# AirScout_SchematicsV0_Spannungsversorgun.net
KiCad netlist of a schematic drawn in Altium Designer
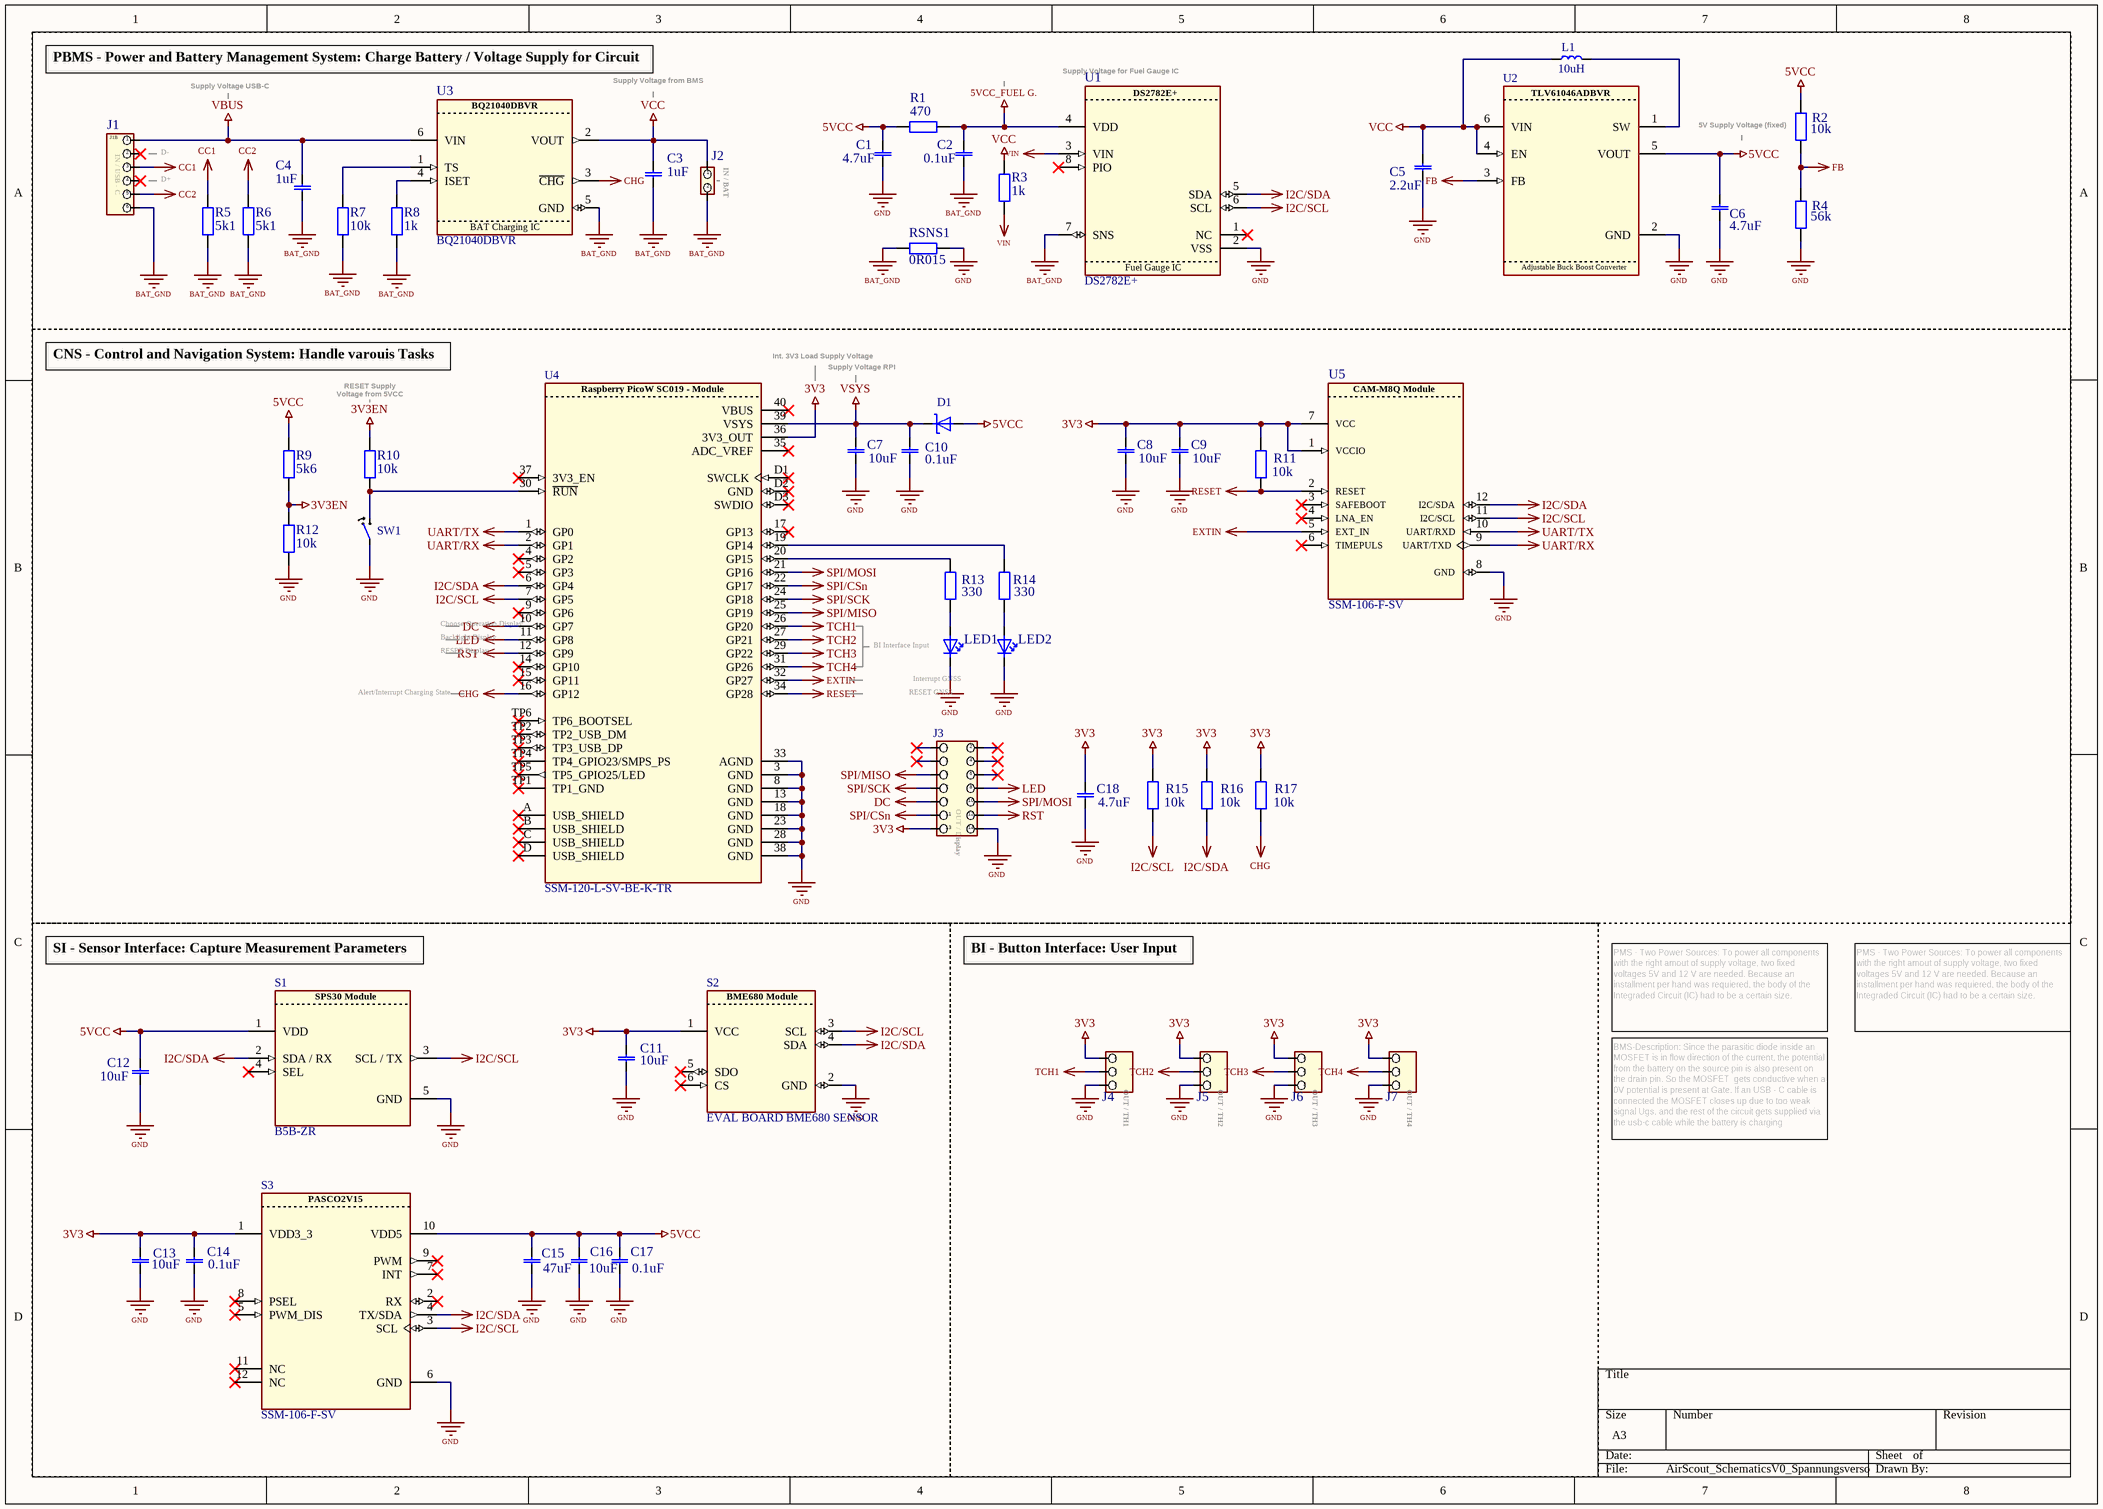
[diagram p0: AirScout_SchematicsV0_Spannungsversorgung.SchDoc]

(export (version "E")
  (design (tool "Eeschema 10.0.6"))
  (components
    (comp (ref "C1")
      (value "4.7uF")
      (footprint "CAPC340180_140N_KEM")
      (description "CAP CER 4.7UF 50V X7R 1206")
      (fields (field (name "Comment") "CL31B475KBHNFNE"))
      (libsource (lib "AirScoutSchLib") (part "CAP"))
    )
    (comp (ref "C2")
      (value "0.1uF")
      (footprint "CAPC340180_140N_KEM")
      (description "CAP CER 0.1UF 50V X7R 1206")
      (fields (field (name "Comment") "C1206C104K5RACTU"))
      (libsource (lib "AirScoutSchLib") (part "CAP"))
    )
    (comp (ref "C3")
      (value "1uF")
      (footprint "CAPC340180_140N_KEM")
      (description "CAP CER 1UF 25V X7R 1206")
      (fields (field (name "Comment") "C1206C105K3RACTU"))
      (libsource (lib "AirScoutSchLib") (part "CAP"))
    )
    (comp (ref "C4")
      (value "1uF")
      (footprint "CAPC340180_140N_KEM")
      (description "CAP CER 1UF 25V X7R 1206")
      (fields (field (name "Comment") "C1206C105K3RACTU"))
      (libsource (lib "AirScoutSchLib") (part "CAP"))
    )
    (comp (ref "C5")
      (value "2.2uF")
      (footprint "CAPC340180_140N_KEM")
      (description "CAP CER 2.2UF 50V X7R 1206")
      (fields (field (name "Comment") "CL31B225KBHNNNE"))
      (libsource (lib "AirScoutSchLib") (part "CAP"))
    )
    (comp (ref "C6")
      (value "4.7uF")
      (footprint "CAPC340180_140N_KEM")
      (description "CAP CER 4.7UF 50V X7R 1206")
      (fields (field (name "Comment") "CL31B475KBHNFNE"))
      (libsource (lib "AirScoutSchLib") (part "CAP"))
    )
    (comp (ref "C7")
      (value "10uF")
      (footprint "CAPC340180_140N_KEM")
      (description "CAP CER 10UF 25V X7R 1206")
      (fields (field (name "Comment") "CL31B106KAHNNNE"))
      (libsource (lib "AirScoutSchLib") (part "CAP"))
    )
    (comp (ref "C8")
      (value "10uF")
      (footprint "CAPC340180_140N_KEM")
      (description "CAP CER 10UF 25V X7R 1206")
      (fields (field (name "Comment") "CL31B106KAHNNNE"))
      (libsource (lib "AirScoutSchLib") (part "CAP"))
    )
    (comp (ref "C9")
      (value "10uF")
      (footprint "CAPC340180_140N_KEM")
      (description "CAP CER 10UF 25V X7R 1206")
      (fields (field (name "Comment") "CL31B106KAHNNNE"))
      (libsource (lib "AirScoutSchLib") (part "CAP"))
    )
    (comp (ref "C10")
      (value "0.1uF")
      (footprint "CAPC340180_140N_KEM")
      (description "CAP CER 0.1UF 50V X7R 1206")
      (fields (field (name "Comment") "C1206C104K5RACTU"))
      (libsource (lib "AirScoutSchLib") (part "CAP"))
    )
    (comp (ref "C11")
      (value "10uF")
      (footprint "CAPC340180_140N_KEM")
      (description "CAP CER 10UF 25V X7R 1206")
      (fields (field (name "Comment") "CL31B106KAHNNNE"))
      (libsource (lib "AirScoutSchLib") (part "CAP"))
    )
    (comp (ref "C12")
      (value "10uF")
      (footprint "CAPC340180_140N_KEM")
      (description "CAP CER 10UF 25V X7R 1206")
      (fields (field (name "Comment") "CL31B106KAHNNNE"))
      (libsource (lib "AirScoutSchLib") (part "CAP"))
    )
    (comp (ref "C13")
      (value "10uF")
      (footprint "CAPC340180_140N_KEM")
      (description "CAP CER 10UF 25V X7R 1206")
      (fields (field (name "Comment") "CL31B106KAHNNNE"))
      (libsource (lib "AirScoutSchLib") (part "CAP"))
    )
    (comp (ref "C14")
      (value "0.1uF")
      (footprint "CAPC340180_140N_KEM")
      (description "CAP CER 0.1UF 50V X7R 1206")
      (fields (field (name "Comment") "C1206C104K5RACTU"))
      (libsource (lib "AirScoutSchLib") (part "CAP"))
    )
    (comp (ref "C15")
      (value "47uF")
      (footprint "CAPC340180_140N_KEM")
      (description "CAP CER 10UF 25V X7R 1206")
      (fields (field (name "Comment") "CL31B106KAHNNNE"))
      (libsource (lib "AirScoutSchLib") (part "CAP"))
    )
    (comp (ref "C16")
      (value "10uF")
      (footprint "CAPC340180_140N_KEM")
      (description "CAP CER 10UF 25V X7R 1206")
      (fields (field (name "Comment") "CL31B106KAHNNNE"))
      (libsource (lib "AirScoutSchLib") (part "CAP"))
    )
    (comp (ref "C17")
      (value "0.1uF")
      (footprint "CAPC340180_140N_KEM")
      (description "CAP CER 0.1UF 50V X7R 1206")
      (fields (field (name "Comment") "C1206C104K5RACTU"))
      (libsource (lib "AirScoutSchLib") (part "CAP"))
    )
    (comp (ref "C18")
      (value "4.7uF")
      (footprint "CAPC340180_140N_KEM")
      (description "CAP CER 4.7UF 50V X7R 1206")
      (fields (field (name "Comment") "CL31B475KBHNFNE"))
      (libsource (lib "AirScoutSchLib") (part "CAP"))
    )
    (comp (ref "D1")
      (value "B240A-13-F")
      (footprint "DIOM5226X230N")
      (description "DIODE SCHOTTKY 40V 2A SMA")
      (libsource (lib "AirScoutSchLib") (part "Diode-Schottky"))
    )
    (comp (ref "J1")
      (value "B6B-PH-K-S")
      (footprint "JST_B6B-PH-K-S")
      (description "CONN HEADER VERT 6POS 2MM")
      (libsource (lib "AirScoutSchLib") (part "CON6x1"))
    )
    (comp (ref "J2")
      (value "B02B-PASK-1")
      (footprint "JST_B2B-PH-K-S")
      (description "CONN HEADER VERT 2POS 2MM")
      (libsource (lib "AirScoutSchLib") (part "CON2x1_vertical"))
    )
    (comp (ref "J3")
      (value "0705430013")
      (footprint "CONN_SDA-70543-XXXX_14_MOL")
      (description "CONN HEADER VERT 14POS 2.54MM")
      (libsource (lib "AirScoutSchLib") (part "CON7x2"))
    )
    (comp (ref "J4")
      (value "0705430002")
      (footprint "MOLEX_70543-0037")
      (description "CONN HEADER VERT 3POS 2.54MM")
      (libsource (lib "AirScoutSchLib") (part "CON 3x1"))
    )
    (comp (ref "J5")
      (value "0705430002")
      (footprint "MOLEX_70543-0037")
      (description "CONN HEADER VERT 3POS 2.54MM")
      (libsource (lib "AirScoutSchLib") (part "CON 3x1"))
    )
    (comp (ref "J6")
      (value "0705430002")
      (footprint "MOLEX_70543-0037")
      (description "CONN HEADER VERT 3POS 2.54MM")
      (libsource (lib "AirScoutSchLib") (part "CON 3x1"))
    )
    (comp (ref "J7")
      (value "0705430002")
      (footprint "MOLEX_70543-0037")
      (description "CONN HEADER VERT 3POS 2.54MM")
      (libsource (lib "AirScoutSchLib") (part "CON 3x1"))
    )
    (comp (ref "L1")
      (value "10uH")
      (footprint "IND_FDSD0420-H-100M=P3")
      (description "FIXED IND 10UH 1.7A 200 MOHM SMD")
      (fields (field (name "Comment") "FDSD0420-H-100M=P3"))
      (libsource (lib "AirScoutSchLib") (part "Inductor"))
    )
    (comp (ref "LED1")
      (value "LTST-C150GKT")
      (footprint "LED_LTST-C150GKT_LTO")
      (description "LED GREEN CLEAR 1206 SMD")
      (libsource (lib "AirScoutSchLib") (part "LED"))
    )
    (comp (ref "LED2")
      (value "LTST-C150KRKT")
      (footprint "LED_LTST-C150GKT_LTO")
      (description "LED RED CLEAR 1206 SMD")
      (libsource (lib "AirScoutSchLib") (part "LED"))
    )
    (comp (ref "R1")
      (value "470")
      (footprint "RESC3116X65N")
      (description "RES 470 OHM 1% 1/4W 1206")
      (fields (field (name "Comment") "CRGCQ1206F470R"))
      (libsource (lib "AirScoutSchLib") (part "RES"))
    )
    (comp (ref "R2")
      (value "10k")
      (footprint "RESC3116X65N")
      (description "RES 10K OHM 1% 1/4W 1206")
      (fields (field (name "Comment") "RC1206FR-0710KL"))
      (libsource (lib "AirScoutSchLib") (part "RES"))
    )
    (comp (ref "R3")
      (value "1k")
      (footprint "RESC3116X65N")
      (description "RES 1K OHM 1% 1/2W 1206")
      (fields (field (name "Comment") "RNCP1206FTD1K00"))
      (libsource (lib "AirScoutSchLib") (part "RES"))
    )
    (comp (ref "R4")
      (value "56k")
      (footprint "RESC3116X65N")
      (description "RES 56K OHM 5% 1/4W 1206")
      (fields (field (name "Comment") "RMCF1206JT56K0"))
      (libsource (lib "AirScoutSchLib") (part "RES"))
    )
    (comp (ref "R5")
      (value "5k1")
      (footprint "RESC3116X65N")
      (description "RES 5.1K OHM 5% 1/4W 1206")
      (fields (field (name "Comment") "RMCF1206JT5K10"))
      (libsource (lib "AirScoutSchLib") (part "RES"))
    )
    (comp (ref "R6")
      (value "5k1")
      (footprint "RESC3116X65N")
      (description "RES 5.1K OHM 5% 1/4W 1206")
      (fields (field (name "Comment") "RMCF1206JT5K10"))
      (libsource (lib "AirScoutSchLib") (part "RES"))
    )
    (comp (ref "R7")
      (value "10k")
      (footprint "RESC3116X65N")
      (description "RES 10K OHM 1% 1/4W 1206")
      (fields (field (name "Comment") "RC1206FR-0710KL"))
      (libsource (lib "AirScoutSchLib") (part "RES"))
    )
    (comp (ref "R8")
      (value "1k")
      (footprint "RESC3116X65N")
      (description "RES 10K OHM 1% 1/4W 1206")
      (fields (field (name "Comment") "RC1206FR-0710KL"))
      (libsource (lib "AirScoutSchLib") (part "RES"))
    )
    (comp (ref "R9")
      (value "5k6")
      (footprint "RESC3116X65N")
      (description "RES 5.6K OHM 5% 1/4W 1206")
      (fields (field (name "Comment") "RC1206JR-075K6L"))
      (libsource (lib "AirScoutSchLib") (part "RES"))
    )
    (comp (ref "R10")
      (value "10k")
      (footprint "RESC3116X65N")
      (description "RES 10K OHM 1% 1/4W 1206")
      (fields (field (name "Comment") "RC1206FR-0710KL"))
      (libsource (lib "AirScoutSchLib") (part "RES"))
    )
    (comp (ref "R11")
      (value "10k")
      (footprint "RESC3116X65N")
      (description "RES 10K OHM 1% 1/4W 1206")
      (fields (field (name "Comment") "RC1206FR-0710KL"))
      (libsource (lib "AirScoutSchLib") (part "RES"))
    )
    (comp (ref "R12")
      (value "10k")
      (footprint "RESC3116X65N")
      (description "RES 10K OHM 1% 1/4W 1206")
      (fields (field (name "Comment") "RC1206FR-0710KL"))
      (libsource (lib "AirScoutSchLib") (part "RES"))
    )
    (comp (ref "R13")
      (value "330")
      (footprint "RESC3116X65N")
      (description "RES 330 OHM 5% 1/4W 1206")
      (fields (field (name "Comment") "RMCF1206JT330R"))
      (libsource (lib "AirScoutSchLib") (part "RES"))
    )
    (comp (ref "R14")
      (value "330")
      (footprint "RESC3116X65N")
      (description "RES 330 OHM 5% 1/4W 1206")
      (fields (field (name "Comment") "RMCF1206JT330R"))
      (libsource (lib "AirScoutSchLib") (part "RES"))
    )
    (comp (ref "R15")
      (value "10k")
      (footprint "RESC3116X65N")
      (description "RES 10K OHM 1% 1/4W 1206")
      (fields (field (name "Comment") "RC1206FR-0710KL"))
      (libsource (lib "AirScoutSchLib") (part "RES"))
    )
    (comp (ref "R16")
      (value "10k")
      (footprint "RESC3116X65N")
      (description "RES 10K OHM 1% 1/4W 1206")
      (fields (field (name "Comment") "RC1206FR-0710KL"))
      (libsource (lib "AirScoutSchLib") (part "RES"))
    )
    (comp (ref "R17")
      (value "10k")
      (footprint "RESC3116X65N")
      (description "RES 10K OHM 1% 1/4W 1206")
      (fields (field (name "Comment") "RC1206FR-0710KL"))
      (libsource (lib "AirScoutSchLib") (part "RES"))
    )
    (comp (ref "RSNS1")
      (value "0R015")
      (footprint "RESC3116X65N")
      (description "RES 0.015 OHM 1% 1/4W 1206")
      (fields (field (name "Comment") "WSL1206R0150FEA"))
      (libsource (lib "AirScoutSchLib") (part "RES"))
    )
    (comp (ref "S1")
      (value "B5B-ZR")
      (footprint "CONN5_B5B-ZR_JST")
      (description "Plug: CONN HEADER VERT 5POS 1.5MM; Air Sensor Dust Sensor Box SPS30 Module: 1649-1106-ND")
      (libsource (lib "AirScoutSchLib") (part "SPS30 Module"))
    )
    (comp (ref "S2")
      (value "EVAL BOARD BME680 SENSOR")
      (footprint "PIM357")
      (description "BME680 - Gas, Feuchtigkeit, Druck, Temperatur Evaluierungsboards - Sensoren")
      (libsource (lib "AirScoutSchLib") (part "BME680 Module"))
    )
    (comp (ref "S3")
      (value "SSM-106-F-SV")
      (footprint "IFX-SMD-LG-MLGA-14-1-V_MODUL")
      (description "(2x) CONN RCPT 6POS 0.1 GOLD SMD; Sensor: EVALCO25VMINIBOARDTOBO1; EVAL BOARD")
      (libsource (lib "AirScoutSchLib") (part "PASCO2V15 Module"))
    )
    (comp (ref "SW1")
      (value "Y97KT23B2NAFP")
      (footprint "SW_PTS647SM38SMTR2LFS_CNK")
      (description "SWITCH TACTILE SPST-NO 0.05A 12V")
      (libsource (lib "AirScoutSchLib") (part "Switch"))
    )
    (comp (ref "U1")
      (value "DS2782E+")
      (footprint "SOP65P640X110-8N")
      (description "UVP (Undervoltageprotection), Battery Battery Monitor IC Lithium Ion/Polymer 8-TSSOP")
      (libsource (lib "AirScoutSchLib") (part "DS2782E+"))
    )
    (comp (ref "U2")
      (value "TLV61046ADBVR")
      (footprint "DBV0006A_M")
      (description "28-V Output Voltage Boost Converter with Power Diode and Isolation Switch 6-SOT-23 -40 to 125")
      (fields (field (name "COPYRIGHT") "Copyright (C) 2025 Ultra Librarian. All rights reserved."))
      (libsource (lib "AirScoutSchLib") (part "TLV61046ADBVR"))
    )
    (comp (ref "U3")
      (value "BQ21040DBVR")
      (footprint "SOT95P280X145-6N")
      (fields (field (name "MF") "Texas Instruments"))
      (libsource (lib "AirScoutSchLib") (part "BQ21040DBVR"))
    )
    (comp (ref "U4")
      (value "SSM-120-L-SV-BE-K-TR")
      (footprint "PicoW SC019")
      (description "(2x) CONN RCPT 20POS 0.1 GOLD SMD; PicoW: SC0918; RASPBERRY PI PICO W RP2040")
      (libsource (lib "AirScoutSchLib") (part "Raspberry PicoW SC019 Module"))
    )
    (comp (ref "U5")
      (value "SSM-106-F-SV")
      (footprint "CAM8MQ-Mod")
      (description "(2x) CONN RCPT 6POS 0.1 GOLD SMD; GPS - Module:  201880; CAM-M8Q-BREAKOUT MULTI GNSS MODU")
      (libsource (lib "AirScoutSchLib") (part "CAM-M8Q Module"))
    )
  )
  (nets
    (net (code "1") (name "3V3") (class "Default")
      (node (ref "C11") (pin "1") (pinfunction "1_1") (pintype "passive"))
      (node (ref "C13") (pin "1") (pinfunction "1_1") (pintype "passive"))
      (node (ref "C14") (pin "1") (pinfunction "1_1") (pintype "passive"))
      (node (ref "C18") (pin "1") (pinfunction "1_1") (pintype "passive"))
      (node (ref "C8") (pin "1") (pinfunction "1_1") (pintype "passive"))
      (node (ref "C9") (pin "1") (pinfunction "1_1") (pintype "passive"))
      (node (ref "J3") (pin "13") (pinfunction "13_13") (pintype "passive"))
      (node (ref "J4") (pin "1") (pinfunction "1_1") (pintype "passive"))
      (node (ref "J5") (pin "1") (pinfunction "1_1") (pintype "passive"))
      (node (ref "J6") (pin "1") (pinfunction "1_1") (pintype "passive"))
      (node (ref "J7") (pin "1") (pinfunction "1_1") (pintype "passive"))
      (node (ref "R11") (pin "2") (pinfunction "2_2") (pintype "passive"))
      (node (ref "R15") (pin "2") (pinfunction "2_2") (pintype "passive"))
      (node (ref "R16") (pin "1") (pinfunction "1_1") (pintype "passive"))
      (node (ref "R17") (pin "1") (pinfunction "1_1") (pintype "passive"))
      (node (ref "S2") (pin "1") (pinfunction "VCC_1") (pintype "power_in"))
      (node (ref "S3") (pin "1") (pinfunction "VDD3_3_1") (pintype "power_in"))
      (node (ref "U4") (pin "36") (pinfunction "3V3_OUT_36") (pintype "power_in"))
      (node (ref "U5") (pin "1") (pinfunction "VCCIO_1") (pintype "input"))
      (node (ref "U5") (pin "7") (pinfunction "VCC_7") (pintype "power_in"))
    )
    (net (code "2") (name "3V3EN") (class "Default")
      (node (ref "R10") (pin "2") (pinfunction "2_2") (pintype "passive"))
      (node (ref "R12") (pin "2") (pinfunction "2_2") (pintype "passive"))
      (node (ref "R9") (pin "1") (pinfunction "1_1") (pintype "passive"))
    )
    (net (code "3") (name "5VCC") (class "Default")
      (node (ref "C1") (pin "1") (pinfunction "1_1") (pintype "passive"))
      (node (ref "C12") (pin "1") (pinfunction "1_1") (pintype "passive"))
      (node (ref "C15") (pin "1") (pinfunction "1_1") (pintype "passive"))
      (node (ref "C16") (pin "1") (pinfunction "1_1") (pintype "passive"))
      (node (ref "C17") (pin "1") (pinfunction "1_1") (pintype "passive"))
      (node (ref "C6") (pin "2") (pinfunction "2_2") (pintype "passive"))
      (node (ref "D1") (pin "A") (pinfunction "A_A") (pintype "passive"))
      (node (ref "R1") (pin "1") (pinfunction "1_1") (pintype "passive"))
      (node (ref "R2") (pin "2") (pinfunction "2_2") (pintype "passive"))
      (node (ref "R9") (pin "2") (pinfunction "2_2") (pintype "passive"))
      (node (ref "S1") (pin "1") (pinfunction "VDD_1") (pintype "passive"))
      (node (ref "S3") (pin "10") (pinfunction "VDD5_10") (pintype "power_in"))
      (node (ref "U2") (pin "5") (pinfunction "VOUT_5") (pintype "power_in"))
    )
    (net (code "4") (name "5VCC_FUEL G.") (class "Default")
      (node (ref "C2") (pin "1") (pinfunction "1_1") (pintype "passive"))
      (node (ref "R1") (pin "2") (pinfunction "2_2") (pintype "passive"))
      (node (ref "U1") (pin "4") (pinfunction "VDD_4") (pintype "power_in"))
    )
    (net (code "5") (name "BAT_GND") (class "Default")
      (node (ref "C2") (pin "2") (pinfunction "2_2") (pintype "passive"))
      (node (ref "C3") (pin "2") (pinfunction "2_2") (pintype "passive"))
      (node (ref "C4") (pin "2") (pinfunction "2_2") (pintype "passive"))
      (node (ref "J1") (pin "6") (pinfunction "6_6") (pintype "passive"))
      (node (ref "J2") (pin "2") (pinfunction "-_2") (pintype "passive"))
      (node (ref "R5") (pin "1") (pinfunction "1_1") (pintype "passive"))
      (node (ref "R6") (pin "1") (pinfunction "1_1") (pintype "passive"))
      (node (ref "R7") (pin "1") (pinfunction "1_1") (pintype "passive"))
      (node (ref "R8") (pin "1") (pinfunction "1_1") (pintype "passive"))
      (node (ref "RSNS1") (pin "2") (pinfunction "2_2") (pintype "passive"))
      (node (ref "U1") (pin "7") (pinfunction "SNS_7") (pintype "bidirectional"))
      (node (ref "U3") (pin "5") (pinfunction "GND_5") (pintype "bidirectional"))
    )
    (net (code "6") (name "CC1") (class "Default")
      (node (ref "J1") (pin "3") (pinfunction "3_3") (pintype "passive"))
      (node (ref "R5") (pin "2") (pinfunction "2_2") (pintype "passive"))
    )
    (net (code "7") (name "CC2") (class "Default")
      (node (ref "J1") (pin "5") (pinfunction "5_5") (pintype "passive"))
      (node (ref "R6") (pin "2") (pinfunction "2_2") (pintype "passive"))
    )
    (net (code "8") (name "CHG") (class "Default")
      (node (ref "R17") (pin "2") (pinfunction "2_2") (pintype "passive"))
      (node (ref "U3") (pin "3") (pinfunction "~{CHG}_3") (pintype "output"))
      (node (ref "U4") (pin "16") (pinfunction "GP12_16") (pintype "bidirectional"))
    )
    (net (code "9") (name "DC") (class "Default")
      (node (ref "J3") (pin "9") (pinfunction "9_9") (pintype "passive"))
      (node (ref "U4") (pin "10") (pinfunction "GP7_10") (pintype "bidirectional"))
    )
    (net (code "10") (name "EXTIN") (class "Default")
      (node (ref "U4") (pin "32") (pinfunction "GP27_32") (pintype "bidirectional"))
      (node (ref "U5") (pin "5") (pinfunction "EXT_IN_5") (pintype "input"))
    )
    (net (code "11") (name "FB") (class "Default")
      (node (ref "R2") (pin "1") (pinfunction "1_1") (pintype "passive"))
      (node (ref "R4") (pin "2") (pinfunction "2_2") (pintype "passive"))
      (node (ref "U2") (pin "3") (pinfunction "FB_3") (pintype "input"))
    )
    (net (code "12") (name "GND") (class "Default")
      (node (ref "C1") (pin "2") (pinfunction "2_2") (pintype "passive"))
      (node (ref "C10") (pin "2") (pinfunction "2_2") (pintype "passive"))
      (node (ref "C11") (pin "2") (pinfunction "2_2") (pintype "passive"))
      (node (ref "C12") (pin "2") (pinfunction "2_2") (pintype "passive"))
      (node (ref "C13") (pin "2") (pinfunction "2_2") (pintype "passive"))
      (node (ref "C14") (pin "2") (pinfunction "2_2") (pintype "passive"))
      (node (ref "C15") (pin "2") (pinfunction "2_2") (pintype "passive"))
      (node (ref "C16") (pin "2") (pinfunction "2_2") (pintype "passive"))
      (node (ref "C17") (pin "2") (pinfunction "2_2") (pintype "passive"))
      (node (ref "C18") (pin "2") (pinfunction "2_2") (pintype "passive"))
      (node (ref "C5") (pin "1") (pinfunction "1_1") (pintype "passive"))
      (node (ref "C6") (pin "1") (pinfunction "1_1") (pintype "passive"))
      (node (ref "C7") (pin "2") (pinfunction "2_2") (pintype "passive"))
      (node (ref "C8") (pin "2") (pinfunction "2_2") (pintype "passive"))
      (node (ref "C9") (pin "2") (pinfunction "2_2") (pintype "passive"))
      (node (ref "J3") (pin "14") (pinfunction "14_14") (pintype "passive"))
      (node (ref "J4") (pin "3") (pinfunction "3_3") (pintype "passive"))
      (node (ref "J5") (pin "3") (pinfunction "3_3") (pintype "passive"))
      (node (ref "J6") (pin "3") (pinfunction "3_3") (pintype "passive"))
      (node (ref "J7") (pin "3") (pinfunction "3_3") (pintype "passive"))
      (node (ref "LED1") (pin "2") (pinfunction "K_2") (pintype "passive"))
      (node (ref "LED2") (pin "2") (pinfunction "K_2") (pintype "passive"))
      (node (ref "R12") (pin "1") (pinfunction "1_1") (pintype "passive"))
      (node (ref "R4") (pin "1") (pinfunction "1_1") (pintype "passive"))
      (node (ref "RSNS1") (pin "1") (pinfunction "1_1") (pintype "passive"))
      (node (ref "S1") (pin "5") (pinfunction "GND_5") (pintype "passive"))
      (node (ref "S2") (pin "2") (pinfunction "GND_2") (pintype "bidirectional"))
      (node (ref "S3") (pin "6") (pinfunction "GND_6") (pintype "power_in"))
      (node (ref "SW1") (pin "1") (pinfunction "1_1") (pintype "passive"))
      (node (ref "U1") (pin "2") (pinfunction "VSS_2") (pintype "power_in"))
      (node (ref "U2") (pin "2") (pinfunction "GND_2") (pintype "power_in"))
      (node (ref "U4") (pin "13") (pinfunction "GND_13") (pintype "power_in"))
      (node (ref "U4") (pin "18") (pinfunction "GND_18") (pintype "power_in"))
      (node (ref "U4") (pin "23") (pinfunction "GND_23") (pintype "power_in"))
      (node (ref "U4") (pin "28") (pinfunction "GND_28") (pintype "power_in"))
      (node (ref "U4") (pin "3") (pinfunction "GND_3") (pintype "power_in"))
      (node (ref "U4") (pin "33") (pinfunction "AGND_33") (pintype "power_in"))
      (node (ref "U4") (pin "38") (pinfunction "GND_38") (pintype "power_in"))
      (node (ref "U4") (pin "8") (pinfunction "GND_8") (pintype "power_in"))
      (node (ref "U5") (pin "8") (pinfunction "GND_8") (pintype "bidirectional"))
    )
    (net (code "13") (name "I2C{slash}SCL") (class "Default")
      (node (ref "R15") (pin "1") (pinfunction "1_1") (pintype "passive"))
      (node (ref "S1") (pin "3") (pinfunction "SCL_/_TX_3") (pintype "output"))
      (node (ref "S2") (pin "3") (pinfunction "SCL_3") (pintype "bidirectional"))
      (node (ref "S3") (pin "3") (pinfunction "SCL_3") (pintype "bidirectional"))
      (node (ref "U1") (pin "6") (pinfunction "SCL_6") (pintype "bidirectional"))
      (node (ref "U4") (pin "7") (pinfunction "GP5_7") (pintype "bidirectional"))
      (node (ref "U5") (pin "11") (pinfunction "I2C/SCL_11") (pintype "bidirectional"))
    )
    (net (code "14") (name "I2C{slash}SDA") (class "Default")
      (node (ref "R16") (pin "2") (pinfunction "2_2") (pintype "passive"))
      (node (ref "S1") (pin "2") (pinfunction "SDA_/_RX_2") (pintype "input"))
      (node (ref "S2") (pin "4") (pinfunction "SDA_4") (pintype "bidirectional"))
      (node (ref "S3") (pin "4") (pinfunction "TX/SDA_4") (pintype "output"))
      (node (ref "U1") (pin "5") (pinfunction "SDA_5") (pintype "bidirectional"))
      (node (ref "U4") (pin "6") (pinfunction "GP4_6") (pintype "bidirectional"))
      (node (ref "U5") (pin "12") (pinfunction "I2C/SDA_12") (pintype "bidirectional"))
    )
    (net (code "15") (name "LED") (class "Default")
      (node (ref "J3") (pin "8") (pinfunction "8_8") (pintype "passive"))
      (node (ref "U4") (pin "11") (pinfunction "GP8_11") (pintype "bidirectional"))
    )
    (net (code "16") (name "Net-(LED1-A)") (class "Default")
      (node (ref "LED1") (pin "1") (pinfunction "A_1") (pintype "passive"))
      (node (ref "R13") (pin "1") (pinfunction "1_1") (pintype "passive"))
    )
    (net (code "17") (name "Net-(LED2-A)") (class "Default")
      (node (ref "LED2") (pin "1") (pinfunction "A_1") (pintype "passive"))
      (node (ref "R14") (pin "1") (pinfunction "1_1") (pintype "passive"))
    )
    (net (code "18") (name "Net-(U2-SW)") (class "Default")
      (node (ref "L1") (pin "2") (pinfunction "2_2") (pintype "passive"))
      (node (ref "U2") (pin "1") (pinfunction "SW_1") (pintype "power_in"))
    )
    (net (code "19") (name "Net-(U3-ISET)") (class "Default")
      (node (ref "R8") (pin "2") (pinfunction "2_2") (pintype "passive"))
      (node (ref "U3") (pin "4") (pinfunction "ISET_4") (pintype "input"))
    )
    (net (code "20") (name "Net-(U3-TS)") (class "Default")
      (node (ref "R7") (pin "2") (pinfunction "2_2") (pintype "passive"))
      (node (ref "U3") (pin "1") (pinfunction "TS_1") (pintype "input"))
    )
    (net (code "21") (name "Net-(U4-GP14)") (class "Default")
      (node (ref "R14") (pin "2") (pinfunction "2_2") (pintype "passive"))
      (node (ref "U4") (pin "19") (pinfunction "GP14_19") (pintype "bidirectional"))
    )
    (net (code "22") (name "Net-(U4-GP15)") (class "Default")
      (node (ref "R13") (pin "2") (pinfunction "2_2") (pintype "passive"))
      (node (ref "U4") (pin "20") (pinfunction "GP15_20") (pintype "bidirectional"))
    )
    (net (code "23") (name "Net-(U4-~{RUN})") (class "Default")
      (node (ref "R10") (pin "1") (pinfunction "1_1") (pintype "passive"))
      (node (ref "SW1") (pin "2") (pinfunction "2_2") (pintype "passive"))
      (node (ref "U4") (pin "30") (pinfunction "~{RUN}_30") (pintype "input"))
    )
    (net (code "24") (name "RESET") (class "Default")
      (node (ref "R11") (pin "1") (pinfunction "1_1") (pintype "passive"))
      (node (ref "U4") (pin "34") (pinfunction "GP28_34") (pintype "bidirectional"))
      (node (ref "U5") (pin "2") (pinfunction "RESET_2") (pintype "input"))
    )
    (net (code "25") (name "RST") (class "Default")
      (node (ref "J3") (pin "12") (pinfunction "12_12") (pintype "passive"))
      (node (ref "U4") (pin "12") (pinfunction "GP9_12") (pintype "bidirectional"))
    )
    (net (code "26") (name "SPI{slash}CSn") (class "Default")
      (node (ref "J3") (pin "11") (pinfunction "11_11") (pintype "passive"))
      (node (ref "U4") (pin "22") (pinfunction "GP17_22") (pintype "bidirectional"))
    )
    (net (code "27") (name "SPI{slash}MISO") (class "Default")
      (node (ref "J3") (pin "5") (pinfunction "5_5") (pintype "passive"))
      (node (ref "U4") (pin "25") (pinfunction "GP19_25") (pintype "bidirectional"))
    )
    (net (code "28") (name "SPI{slash}MOSI") (class "Default")
      (node (ref "J3") (pin "10") (pinfunction "10_10") (pintype "passive"))
      (node (ref "U4") (pin "21") (pinfunction "GP16_21") (pintype "bidirectional"))
    )
    (net (code "29") (name "SPI{slash}SCK") (class "Default")
      (node (ref "J3") (pin "7") (pinfunction "7_7") (pintype "passive"))
      (node (ref "U4") (pin "24") (pinfunction "GP18_24") (pintype "bidirectional"))
    )
    (net (code "30") (name "TCH1") (class "Default")
      (node (ref "J4") (pin "2") (pinfunction "2_2") (pintype "passive"))
      (node (ref "U4") (pin "26") (pinfunction "GP20_26") (pintype "bidirectional"))
    )
    (net (code "31") (name "TCH2") (class "Default")
      (node (ref "J5") (pin "2") (pinfunction "2_2") (pintype "passive"))
      (node (ref "U4") (pin "27") (pinfunction "GP21_27") (pintype "bidirectional"))
    )
    (net (code "32") (name "TCH3") (class "Default")
      (node (ref "J6") (pin "2") (pinfunction "2_2") (pintype "passive"))
      (node (ref "U4") (pin "29") (pinfunction "GP22_29") (pintype "bidirectional"))
    )
    (net (code "33") (name "TCH4") (class "Default")
      (node (ref "J7") (pin "2") (pinfunction "2_2") (pintype "passive"))
      (node (ref "U4") (pin "31") (pinfunction "GP26_31") (pintype "bidirectional"))
    )
    (net (code "34") (name "UART{slash}RX") (class "Default")
      (node (ref "U4") (pin "2") (pinfunction "GP1_2") (pintype "bidirectional"))
      (node (ref "U5") (pin "9") (pinfunction "UART/TXD_9") (pintype "output"))
    )
    (net (code "35") (name "UART{slash}TX") (class "Default")
      (node (ref "U4") (pin "1") (pinfunction "GP0_1") (pintype "bidirectional"))
      (node (ref "U5") (pin "10") (pinfunction "UART/RXD_10") (pintype "input"))
    )
    (net (code "36") (name "VBUS") (class "Default")
      (node (ref "C4") (pin "1") (pinfunction "1_1") (pintype "passive"))
      (node (ref "J1") (pin "1") (pinfunction "1_1") (pintype "passive"))
      (node (ref "U3") (pin "6") (pinfunction "VIN_6") (pintype "power_in"))
    )
    (net (code "37") (name "VCC") (class "Default")
      (node (ref "C3") (pin "1") (pinfunction "1_1") (pintype "passive"))
      (node (ref "C5") (pin "2") (pinfunction "2_2") (pintype "passive"))
      (node (ref "J2") (pin "1") (pinfunction "+_1") (pintype "passive"))
      (node (ref "L1") (pin "1") (pinfunction "1_1") (pintype "passive"))
      (node (ref "R3") (pin "2") (pinfunction "2_2") (pintype "passive"))
      (node (ref "U2") (pin "4") (pinfunction "EN_4") (pintype "input"))
      (node (ref "U2") (pin "6") (pinfunction "VIN_6") (pintype "power_in"))
      (node (ref "U3") (pin "2") (pinfunction "VOUT_2") (pintype "output"))
    )
    (net (code "38") (name "VIN") (class "Default")
      (node (ref "R3") (pin "1") (pinfunction "1_1") (pintype "passive"))
      (node (ref "U1") (pin "3") (pinfunction "VIN_3") (pintype "input"))
    )
    (net (code "39") (name "VSYS") (class "Default")
      (node (ref "C10") (pin "1") (pinfunction "1_1") (pintype "passive"))
      (node (ref "C7") (pin "1") (pinfunction "1_1") (pintype "passive"))
      (node (ref "D1") (pin "K") (pinfunction "K_K") (pintype "passive"))
      (node (ref "U4") (pin "39") (pinfunction "VSYS_39") (pintype "power_in"))
    )
    (net (code "40") (name "unconnected-(J1-Pad2)") (class "Default")
      (node (ref "J1") (pin "2") (pinfunction "2_2") (pintype "passive+no_connect"))
    )
    (net (code "41") (name "unconnected-(J1-Pad4)") (class "Default")
      (node (ref "J1") (pin "4") (pinfunction "4_4") (pintype "passive+no_connect"))
    )
    (net (code "42") (name "unconnected-(J3-Pad1)") (class "Default")
      (node (ref "J3") (pin "1") (pinfunction "1_1") (pintype "passive+no_connect"))
    )
    (net (code "43") (name "unconnected-(J3-Pad2)") (class "Default")
      (node (ref "J3") (pin "2") (pinfunction "2_2") (pintype "passive+no_connect"))
    )
    (net (code "44") (name "unconnected-(J3-Pad3)") (class "Default")
      (node (ref "J3") (pin "3") (pinfunction "3_3") (pintype "passive+no_connect"))
    )
    (net (code "45") (name "unconnected-(J3-Pad4)") (class "Default")
      (node (ref "J3") (pin "4") (pinfunction "4_4") (pintype "passive+no_connect"))
    )
    (net (code "46") (name "unconnected-(J3-Pad6)") (class "Default")
      (node (ref "J3") (pin "6") (pinfunction "6_6") (pintype "passive+no_connect"))
    )
    (net (code "47") (name "unconnected-(S1-SEL-Pad4)") (class "Default")
      (node (ref "S1") (pin "4") (pinfunction "SEL_4") (pintype "input+no_connect"))
    )
    (net (code "48") (name "unconnected-(S2-CS-Pad6)") (class "Default")
      (node (ref "S2") (pin "6") (pinfunction "CS_6") (pintype "input+no_connect"))
    )
    (net (code "49") (name "unconnected-(S2-SDO-Pad5)") (class "Default")
      (node (ref "S2") (pin "5") (pinfunction "SDO_5") (pintype "bidirectional+no_connect"))
    )
    (net (code "50") (name "unconnected-(S3-INT-Pad7)") (class "Default")
      (node (ref "S3") (pin "7") (pinfunction "INT_7") (pintype "output+no_connect"))
    )
    (net (code "51") (name "unconnected-(S3-NC-Pad11)") (class "Default")
      (node (ref "S3") (pin "11") (pinfunction "NC_11") (pintype "power_in+no_connect"))
    )
    (net (code "52") (name "unconnected-(S3-NC-Pad12)") (class "Default")
      (node (ref "S3") (pin "12") (pinfunction "NC_12") (pintype "passive+no_connect"))
    )
    (net (code "53") (name "unconnected-(S3-PSEL-Pad8)") (class "Default")
      (node (ref "S3") (pin "8") (pinfunction "PSEL_8") (pintype "input+no_connect"))
    )
    (net (code "54") (name "unconnected-(S3-PWM-Pad9)") (class "Default")
      (node (ref "S3") (pin "9") (pinfunction "PWM_9") (pintype "output+no_connect"))
    )
    (net (code "55") (name "unconnected-(S3-PWM_DIS-Pad5)") (class "Default")
      (node (ref "S3") (pin "5") (pinfunction "PWM_DIS_5") (pintype "input+no_connect"))
    )
    (net (code "56") (name "unconnected-(S3-RX-Pad2)") (class "Default")
      (node (ref "S3") (pin "2") (pinfunction "RX_2") (pintype "bidirectional+no_connect"))
    )
    (net (code "57") (name "unconnected-(U1-NC-Pad1)") (class "Default")
      (node (ref "U1") (pin "1") (pinfunction "NC_1") (pintype "power_in+no_connect"))
    )
    (net (code "58") (name "unconnected-(U1-PIO-Pad8)") (class "Default")
      (node (ref "U1") (pin "8") (pinfunction "PIO_8") (pintype "input+no_connect"))
    )
    (net (code "59") (name "unconnected-(U4-3V3_EN-Pad37)") (class "Default")
      (node (ref "U4") (pin "37") (pinfunction "3V3_EN_37") (pintype "input+no_connect"))
    )
    (net (code "60") (name "unconnected-(U4-ADC_VREF-Pad35)") (class "Default")
      (node (ref "U4") (pin "35") (pinfunction "ADC_VREF_35") (pintype "power_in+no_connect"))
    )
    (net (code "61") (name "unconnected-(U4-GND-PadD2)") (class "Default")
      (node (ref "U4") (pin "D2") (pinfunction "GND_D2") (pintype "bidirectional+no_connect"))
    )
    (net (code "62") (name "unconnected-(U4-GP2-Pad4)") (class "Default")
      (node (ref "U4") (pin "4") (pinfunction "GP2_4") (pintype "bidirectional+no_connect"))
    )
    (net (code "63") (name "unconnected-(U4-GP3-Pad5)") (class "Default")
      (node (ref "U4") (pin "5") (pinfunction "GP3_5") (pintype "bidirectional+no_connect"))
    )
    (net (code "64") (name "unconnected-(U4-GP6-Pad9)") (class "Default")
      (node (ref "U4") (pin "9") (pinfunction "GP6_9") (pintype "bidirectional+no_connect"))
    )
    (net (code "65") (name "unconnected-(U4-GP10-Pad14)") (class "Default")
      (node (ref "U4") (pin "14") (pinfunction "GP10_14") (pintype "bidirectional+no_connect"))
    )
    (net (code "66") (name "unconnected-(U4-GP11-Pad15)") (class "Default")
      (node (ref "U4") (pin "15") (pinfunction "GP11_15") (pintype "bidirectional+no_connect"))
    )
    (net (code "67") (name "unconnected-(U4-GP13-Pad17)") (class "Default")
      (node (ref "U4") (pin "17") (pinfunction "GP13_17") (pintype "bidirectional+no_connect"))
    )
    (net (code "68") (name "unconnected-(U4-SWCLK-PadD1)") (class "Default")
      (node (ref "U4") (pin "D1") (pinfunction "SWCLK_D1") (pintype "input+no_connect"))
    )
    (net (code "69") (name "unconnected-(U4-SWDIO-PadD3)") (class "Default")
      (node (ref "U4") (pin "D3") (pinfunction "SWDIO_D3") (pintype "bidirectional+no_connect"))
    )
    (net (code "70") (name "unconnected-(U4-TP1_GND-PadTP1)") (class "Default")
      (node (ref "U4") (pin "TP1") (pinfunction "TP1_GND_TP1") (pintype "power_in+no_connect"))
    )
    (net (code "71") (name "unconnected-(U4-TP2_USB_DM-PadTP2)") (class "Default")
      (node (ref "U4") (pin "TP2") (pinfunction "TP2_USB_DM_TP2") (pintype "bidirectional+no_connect"))
    )
    (net (code "72") (name "unconnected-(U4-TP3_USB_DP-PadTP3)") (class "Default")
      (node (ref "U4") (pin "TP3") (pinfunction "TP3_USB_DP_TP3") (pintype "bidirectional+no_connect"))
    )
    (net (code "73") (name "unconnected-(U4-TP4_GPIO23{slash}SMPS_PS-PadTP4)") (class "Default")
      (node (ref "U4") (pin "TP4") (pinfunction "TP4_GPIO23/SMPS_PS_TP4") (pintype "passive+no_connect"))
    )
    (net (code "74") (name "unconnected-(U4-TP5_GPIO25{slash}LED-PadTP5)") (class "Default")
      (node (ref "U4") (pin "TP5") (pinfunction "TP5_GPIO25/LED_TP5") (pintype "output+no_connect"))
    )
    (net (code "75") (name "unconnected-(U4-TP6_BOOTSEL-PadTP6)") (class "Default")
      (node (ref "U4") (pin "TP6") (pinfunction "TP6_BOOTSEL_TP6") (pintype "input+no_connect"))
    )
    (net (code "76") (name "unconnected-(U4-USB_SHIELD-PadA)") (class "Default")
      (node (ref "U4") (pin "A") (pinfunction "USB_SHIELD_A") (pintype "power_in+no_connect"))
    )
    (net (code "77") (name "unconnected-(U4-USB_SHIELD-PadB)") (class "Default")
      (node (ref "U4") (pin "B") (pinfunction "USB_SHIELD_B") (pintype "power_in+no_connect"))
    )
    (net (code "78") (name "unconnected-(U4-USB_SHIELD-PadC)") (class "Default")
      (node (ref "U4") (pin "C") (pinfunction "USB_SHIELD_C") (pintype "power_in+no_connect"))
    )
    (net (code "79") (name "unconnected-(U4-USB_SHIELD-PadD)") (class "Default")
      (node (ref "U4") (pin "D") (pinfunction "USB_SHIELD_D") (pintype "power_in+no_connect"))
    )
    (net (code "80") (name "unconnected-(U4-VBUS-Pad40)") (class "Default")
      (node (ref "U4") (pin "40") (pinfunction "VBUS_40") (pintype "power_in+no_connect"))
    )
    (net (code "81") (name "unconnected-(U5-LNA_EN-Pad4)") (class "Default")
      (node (ref "U5") (pin "4") (pinfunction "LNA_EN_4") (pintype "input+no_connect"))
    )
    (net (code "82") (name "unconnected-(U5-SAFEBOOT-Pad3)") (class "Default")
      (node (ref "U5") (pin "3") (pinfunction "SAFEBOOT_3") (pintype "input+no_connect"))
    )
    (net (code "83") (name "unconnected-(U5-TIMEPULS-Pad6)") (class "Default")
      (node (ref "U5") (pin "6") (pinfunction "TIMEPULS_6") (pintype "input+no_connect"))
    )
  )
)
